# backpack_board.net
KiCad netlist of a schematic drawn in EAGLE
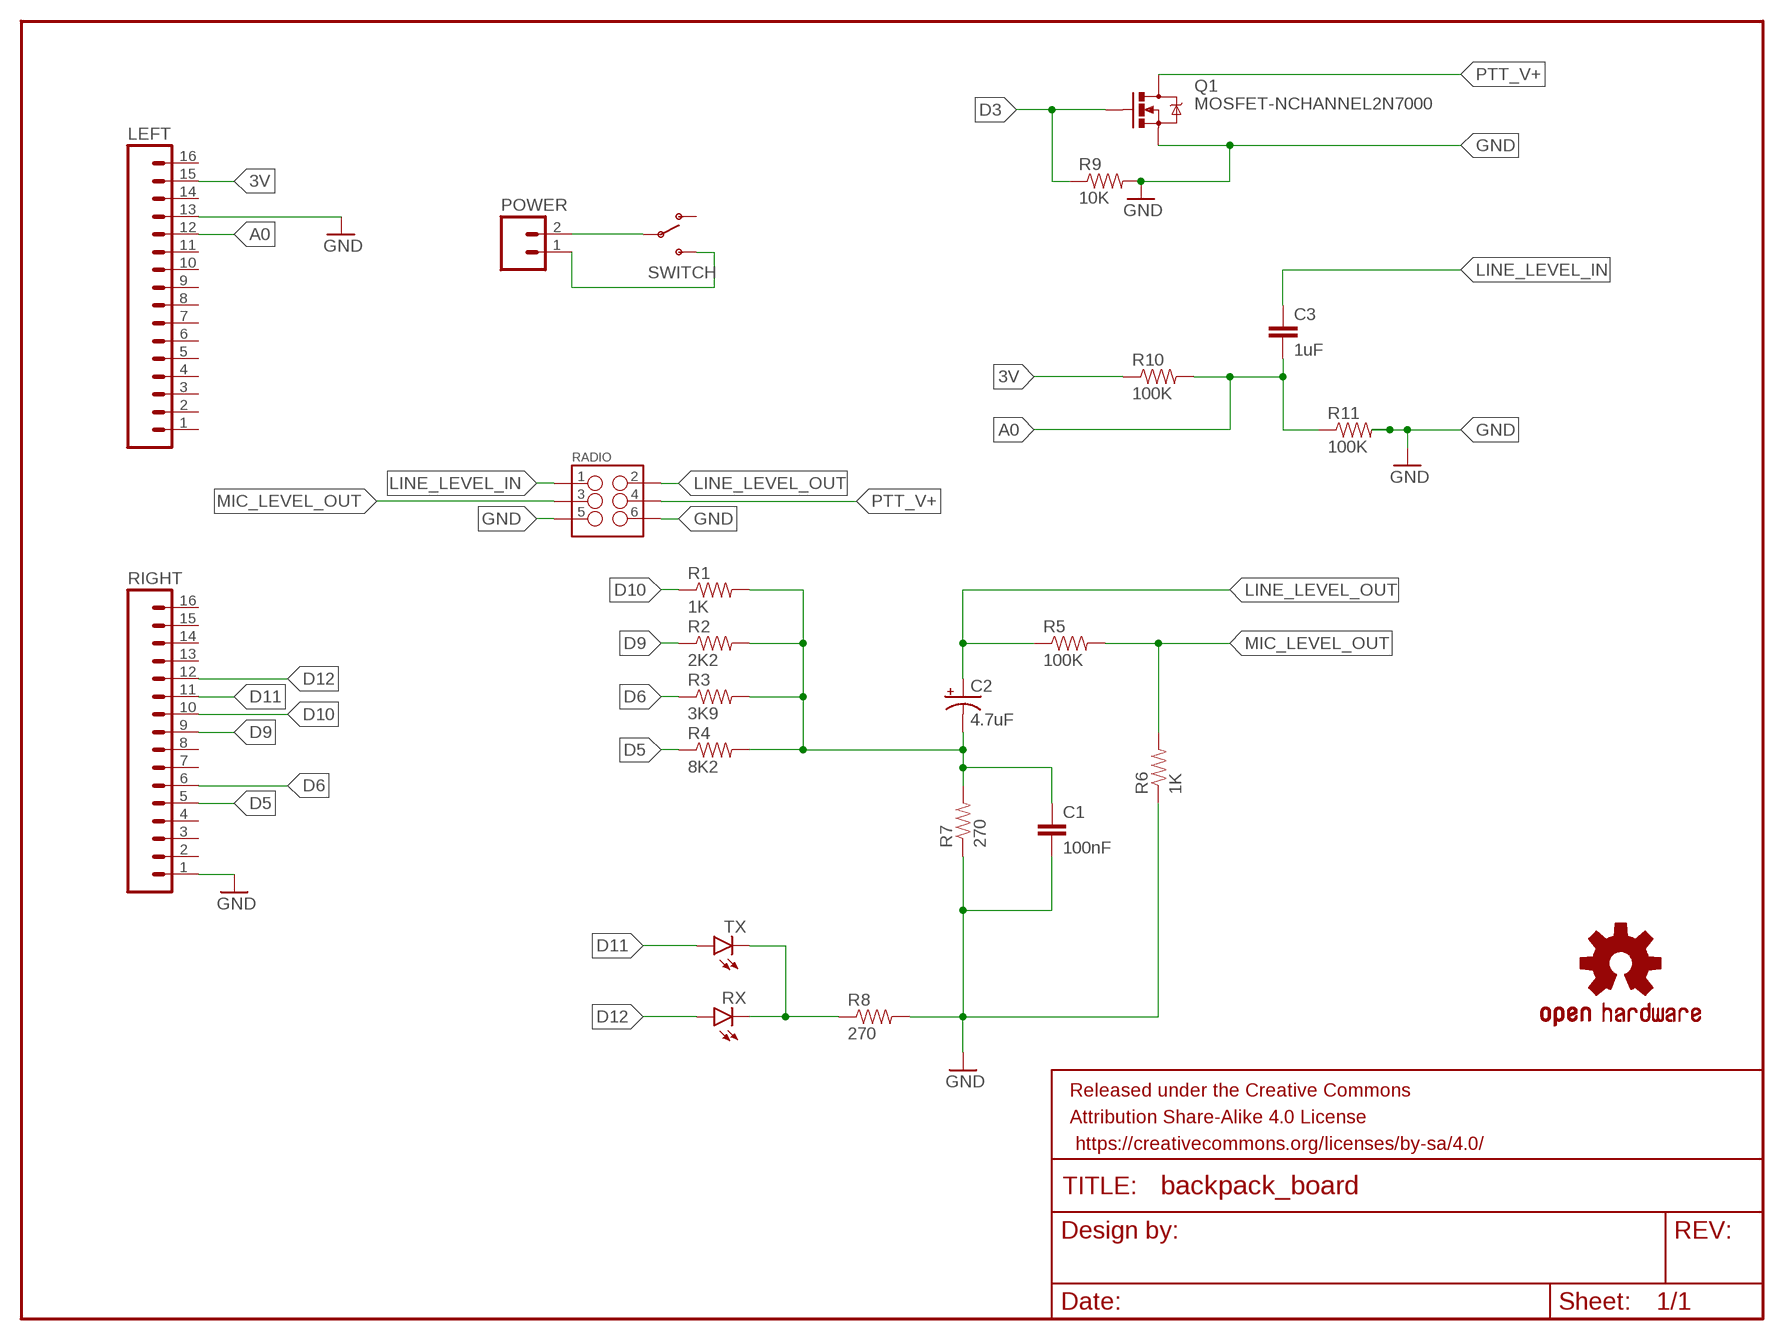
[diagram p0: schematic, sheet 1]

(export (version "E")
  (design (tool "Eeschema 10.0.6"))
  (components
    (comp (ref "C1")
      (value "100nF")
      (footprint "eagle-import:CAP-PTH-SMALL")
      (libsource (lib "eagle-import") (part "CAPPTH"))
    )
    (comp (ref "C2")
      (value "4.7uF")
      (footprint "eagle-import:CPOL-RADIAL-10UF-25V")
      (libsource (lib "eagle-import") (part "CAP_POLPTH2"))
    )
    (comp (ref "C3")
      (value "1uF")
      (footprint "eagle-import:CAP-PTH-SMALL")
      (libsource (lib "eagle-import") (part "CAPPTH"))
    )
    (comp (ref "FRAME1")
      (value "FRAME-LETTERNO_PACKAGE")
      (footprint "eagle-import:DUMMY")
      (fields (field (name "DESIGNER") "Nobody"))
      (libsource (lib "eagle-import") (part "FRAME-LETTERNO_PACKAGE"))
    )
    (comp (ref "LEFT")
      (value "M16PTH")
      (footprint "eagle-import:1X16")
      (libsource (lib "eagle-import") (part "M16PTH"))
    )
    (comp (ref "LOGO1")
      (value "OSHW-LOGOM")
      (footprint "eagle-import:OSHW-LOGO-M")
      (libsource (lib "eagle-import") (part "OSHW-LOGOM"))
    )
    (comp (ref "POWER")
      (value "M02PTH")
      (footprint "eagle-import:1X02")
      (libsource (lib "eagle-import") (part "M02PTH"))
    )
    (comp (ref "Q1")
      (value "MOSFET-NCHANNEL2N7000")
      (footprint "eagle-import:TO-92")
      (libsource (lib "eagle-import") (part "MOSFET-NCHANNEL2N7000"))
    )
    (comp (ref "R1")
      (value "1K")
      (footprint "eagle-import:AXIAL-0.4")
      (libsource (lib "eagle-import") (part "RESISTORPTH-1/4W"))
    )
    (comp (ref "R2")
      (value "2K2")
      (footprint "eagle-import:AXIAL-0.4")
      (libsource (lib "eagle-import") (part "RESISTORPTH-1/4W"))
    )
    (comp (ref "R3")
      (value "3K9")
      (footprint "eagle-import:AXIAL-0.4")
      (libsource (lib "eagle-import") (part "RESISTORPTH-1/4W"))
    )
    (comp (ref "R4")
      (value "8K2")
      (footprint "eagle-import:AXIAL-0.4")
      (libsource (lib "eagle-import") (part "RESISTORPTH-1/4W"))
    )
    (comp (ref "R5")
      (value "100K")
      (footprint "eagle-import:AXIAL-0.4")
      (libsource (lib "eagle-import") (part "RESISTORPTH-1/4W"))
    )
    (comp (ref "R6")
      (value "1K")
      (footprint "eagle-import:AXIAL-0.4")
      (libsource (lib "eagle-import") (part "RESISTORPTH-1/4W"))
    )
    (comp (ref "R7")
      (value "270")
      (footprint "eagle-import:AXIAL-0.4")
      (libsource (lib "eagle-import") (part "RESISTORPTH-1/4W"))
    )
    (comp (ref "R8")
      (value "270")
      (footprint "eagle-import:AXIAL-0.4")
      (libsource (lib "eagle-import") (part "RESISTORPTH-1/4W"))
    )
    (comp (ref "R9")
      (value "10K")
      (footprint "eagle-import:AXIAL-0.4")
      (libsource (lib "eagle-import") (part "RESISTORPTH-1/4W"))
    )
    (comp (ref "R10")
      (value "100K")
      (footprint "eagle-import:AXIAL-0.4")
      (libsource (lib "eagle-import") (part "RESISTORPTH-1/4W"))
    )
    (comp (ref "R11")
      (value "100K")
      (footprint "eagle-import:AXIAL-0.4")
      (libsource (lib "eagle-import") (part "RESISTORPTH-1/4W"))
    )
    (comp (ref "RADIO")
      (value "M03X2FEMALE")
      (footprint "eagle-import:2X3")
      (libsource (lib "eagle-import") (part "M03X2FEMALE"))
    )
    (comp (ref "RIGHT")
      (value "M16PTH")
      (footprint "eagle-import:1X16")
      (libsource (lib "eagle-import") (part "M16PTH"))
    )
    (comp (ref "RX")
      (value "LED3MM")
      (footprint "eagle-import:LED3MM")
      (libsource (lib "eagle-import") (part "LED3MM"))
    )
    (comp (ref "SWITCH")
      (value "SWITCH-SPDTPTH")
      (footprint "eagle-import:SWITCH-SPDT")
      (libsource (lib "eagle-import") (part "SWITCH-SPDTPTH"))
    )
    (comp (ref "TX")
      (value "LED3MM")
      (footprint "eagle-import:LED3MM")
      (libsource (lib "eagle-import") (part "LED3MM"))
    )
  )
  (nets
    (net (code "1") (name "3V") (class "Default")
      (node (ref "LEFT") (pin "15") (pinfunction "15_15") (pintype "passive"))
      (node (ref "R10") (pin "P$1") (pinfunction "1_P$1") (pintype "passive"))
    )
    (net (code "2") (name "A0") (class "Default")
      (node (ref "C3") (pin "2") (pinfunction "2_2") (pintype "passive"))
      (node (ref "LEFT") (pin "12") (pinfunction "12_12") (pintype "passive"))
      (node (ref "R10") (pin "P$2") (pinfunction "2_P$2") (pintype "passive"))
      (node (ref "R11") (pin "P$1") (pinfunction "1_P$1") (pintype "passive"))
    )
    (net (code "3") (name "D3") (class "Default")
      (node (ref "Q1") (pin "2") (pinfunction "G_2") (pintype "passive"))
      (node (ref "R9") (pin "P$1") (pinfunction "1_P$1") (pintype "passive"))
    )
    (net (code "4") (name "D5") (class "Default")
      (node (ref "R4") (pin "P$1") (pinfunction "1_P$1") (pintype "passive"))
      (node (ref "RIGHT") (pin "5") (pinfunction "5_5") (pintype "passive"))
    )
    (net (code "5") (name "D6") (class "Default")
      (node (ref "R3") (pin "P$1") (pinfunction "1_P$1") (pintype "passive"))
      (node (ref "RIGHT") (pin "6") (pinfunction "6_6") (pintype "passive"))
    )
    (net (code "6") (name "D9") (class "Default")
      (node (ref "R2") (pin "P$1") (pinfunction "1_P$1") (pintype "passive"))
      (node (ref "RIGHT") (pin "9") (pinfunction "9_9") (pintype "passive"))
    )
    (net (code "7") (name "D10") (class "Default")
      (node (ref "R1") (pin "P$1") (pinfunction "1_P$1") (pintype "passive"))
      (node (ref "RIGHT") (pin "10") (pinfunction "10_10") (pintype "passive"))
    )
    (net (code "8") (name "D11") (class "Default")
      (node (ref "RIGHT") (pin "11") (pinfunction "11_11") (pintype "passive"))
      (node (ref "TX") (pin "A") (pinfunction "A_A") (pintype "passive"))
    )
    (net (code "9") (name "D12") (class "Default")
      (node (ref "RIGHT") (pin "12") (pinfunction "12_12") (pintype "passive"))
      (node (ref "RX") (pin "A") (pinfunction "A_A") (pintype "passive"))
    )
    (net (code "10") (name "GND") (class "Default")
      (node (ref "C1") (pin "2") (pinfunction "2_2") (pintype "passive"))
      (node (ref "LEFT") (pin "13") (pinfunction "13_13") (pintype "passive"))
      (node (ref "Q1") (pin "1") (pinfunction "S_1") (pintype "passive"))
      (node (ref "R11") (pin "P$2") (pinfunction "2_P$2") (pintype "passive"))
      (node (ref "R6") (pin "P$1") (pinfunction "1_P$1") (pintype "passive"))
      (node (ref "R7") (pin "P$1") (pinfunction "1_P$1") (pintype "passive"))
      (node (ref "R8") (pin "P$2") (pinfunction "2_P$2") (pintype "passive"))
      (node (ref "R9") (pin "P$2") (pinfunction "2_P$2") (pintype "passive"))
      (node (ref "RADIO") (pin "5") (pinfunction "5_5") (pintype "bidirectional"))
      (node (ref "RADIO") (pin "6") (pinfunction "6_6") (pintype "bidirectional"))
      (node (ref "RIGHT") (pin "1") (pinfunction "1_1") (pintype "passive"))
    )
    (net (code "11") (name "LINE_LEVEL_IN") (class "Default")
      (node (ref "C3") (pin "1") (pinfunction "1_1") (pintype "passive"))
      (node (ref "RADIO") (pin "1") (pinfunction "1_1") (pintype "bidirectional"))
    )
    (net (code "12") (name "LINE_LEVEL_OUT") (class "Default")
      (node (ref "C2") (pin "1") (pinfunction "+_1") (pintype "passive"))
      (node (ref "R5") (pin "P$1") (pinfunction "1_P$1") (pintype "passive"))
      (node (ref "RADIO") (pin "2") (pinfunction "2_2") (pintype "bidirectional"))
    )
    (net (code "13") (name "MIC_LEVEL_OUT") (class "Default")
      (node (ref "R5") (pin "P$2") (pinfunction "2_P$2") (pintype "passive"))
      (node (ref "R6") (pin "P$2") (pinfunction "2_P$2") (pintype "passive"))
      (node (ref "RADIO") (pin "3") (pinfunction "3_3") (pintype "bidirectional"))
    )
    (net (code "14") (name "Net-(C2--)") (class "Default")
      (node (ref "C1") (pin "1") (pinfunction "1_1") (pintype "passive"))
      (node (ref "C2") (pin "2") (pinfunction "-_2") (pintype "passive"))
      (node (ref "R1") (pin "P$2") (pinfunction "2_P$2") (pintype "passive"))
      (node (ref "R2") (pin "P$2") (pinfunction "2_P$2") (pintype "passive"))
      (node (ref "R3") (pin "P$2") (pinfunction "2_P$2") (pintype "passive"))
      (node (ref "R4") (pin "P$2") (pinfunction "2_P$2") (pintype "passive"))
      (node (ref "R7") (pin "P$2") (pinfunction "2_P$2") (pintype "passive"))
    )
    (net (code "15") (name "Net-(R8-1)") (class "Default")
      (node (ref "R8") (pin "P$1") (pinfunction "1_P$1") (pintype "passive"))
      (node (ref "RX") (pin "K") (pinfunction "C_K") (pintype "passive"))
      (node (ref "TX") (pin "K") (pinfunction "C_K") (pintype "passive"))
    )
    (net (code "16") (name "Net-(SWITCH-P)") (class "Default")
      (node (ref "POWER") (pin "2") (pinfunction "2_2") (pintype "passive"))
      (node (ref "SWITCH") (pin "2") (pinfunction "P_2") (pintype "passive"))
    )
    (net (code "17") (name "Net-(SWITCH-S)") (class "Default")
      (node (ref "POWER") (pin "1") (pinfunction "1_1") (pintype "passive"))
      (node (ref "SWITCH") (pin "3") (pinfunction "S_3") (pintype "passive"))
    )
    (net (code "18") (name "PTT_V+") (class "Default")
      (node (ref "Q1") (pin "3") (pinfunction "D_3") (pintype "passive"))
      (node (ref "RADIO") (pin "4") (pinfunction "4_4") (pintype "bidirectional"))
    )
    (net (code "19") (name "unconnected-(LEFT-Pad1)") (class "Default")
      (node (ref "LEFT") (pin "1") (pinfunction "1_1") (pintype "passive"))
    )
    (net (code "20") (name "unconnected-(LEFT-Pad2)") (class "Default")
      (node (ref "LEFT") (pin "2") (pinfunction "2_2") (pintype "passive"))
    )
    (net (code "21") (name "unconnected-(LEFT-Pad3)") (class "Default")
      (node (ref "LEFT") (pin "3") (pinfunction "3_3") (pintype "passive"))
    )
    (net (code "22") (name "unconnected-(LEFT-Pad4)") (class "Default")
      (node (ref "LEFT") (pin "4") (pinfunction "4_4") (pintype "passive"))
    )
    (net (code "23") (name "unconnected-(LEFT-Pad5)") (class "Default")
      (node (ref "LEFT") (pin "5") (pinfunction "5_5") (pintype "passive"))
    )
    (net (code "24") (name "unconnected-(LEFT-Pad6)") (class "Default")
      (node (ref "LEFT") (pin "6") (pinfunction "6_6") (pintype "passive"))
    )
    (net (code "25") (name "unconnected-(LEFT-Pad7)") (class "Default")
      (node (ref "LEFT") (pin "7") (pinfunction "7_7") (pintype "passive"))
    )
    (net (code "26") (name "unconnected-(LEFT-Pad8)") (class "Default")
      (node (ref "LEFT") (pin "8") (pinfunction "8_8") (pintype "passive"))
    )
    (net (code "27") (name "unconnected-(LEFT-Pad9)") (class "Default")
      (node (ref "LEFT") (pin "9") (pinfunction "9_9") (pintype "passive"))
    )
    (net (code "28") (name "unconnected-(LEFT-Pad10)") (class "Default")
      (node (ref "LEFT") (pin "10") (pinfunction "10_10") (pintype "passive"))
    )
    (net (code "29") (name "unconnected-(LEFT-Pad11)") (class "Default")
      (node (ref "LEFT") (pin "11") (pinfunction "11_11") (pintype "passive"))
    )
    (net (code "30") (name "unconnected-(LEFT-Pad14)") (class "Default")
      (node (ref "LEFT") (pin "14") (pinfunction "14_14") (pintype "passive"))
    )
    (net (code "31") (name "unconnected-(LEFT-Pad16)") (class "Default")
      (node (ref "LEFT") (pin "16") (pinfunction "16_16") (pintype "passive"))
    )
    (net (code "32") (name "unconnected-(RIGHT-Pad2)") (class "Default")
      (node (ref "RIGHT") (pin "2") (pinfunction "2_2") (pintype "passive"))
    )
    (net (code "33") (name "unconnected-(RIGHT-Pad3)") (class "Default")
      (node (ref "RIGHT") (pin "3") (pinfunction "3_3") (pintype "passive"))
    )
    (net (code "34") (name "unconnected-(RIGHT-Pad4)") (class "Default")
      (node (ref "RIGHT") (pin "4") (pinfunction "4_4") (pintype "passive"))
    )
    (net (code "35") (name "unconnected-(RIGHT-Pad7)") (class "Default")
      (node (ref "RIGHT") (pin "7") (pinfunction "7_7") (pintype "passive"))
    )
    (net (code "36") (name "unconnected-(RIGHT-Pad8)") (class "Default")
      (node (ref "RIGHT") (pin "8") (pinfunction "8_8") (pintype "passive"))
    )
    (net (code "37") (name "unconnected-(RIGHT-Pad13)") (class "Default")
      (node (ref "RIGHT") (pin "13") (pinfunction "13_13") (pintype "passive"))
    )
    (net (code "38") (name "unconnected-(RIGHT-Pad14)") (class "Default")
      (node (ref "RIGHT") (pin "14") (pinfunction "14_14") (pintype "passive"))
    )
    (net (code "39") (name "unconnected-(RIGHT-Pad15)") (class "Default")
      (node (ref "RIGHT") (pin "15") (pinfunction "15_15") (pintype "passive"))
    )
    (net (code "40") (name "unconnected-(RIGHT-Pad16)") (class "Default")
      (node (ref "RIGHT") (pin "16") (pinfunction "16_16") (pintype "passive"))
    )
    (net (code "41") (name "unconnected-(SWITCH-O-Pad1)") (class "Default")
      (node (ref "SWITCH") (pin "1") (pinfunction "O_1") (pintype "passive"))
    )
  )
)
